# picospeaker.net
KiCad netlist of a schematic drawn in EAGLE
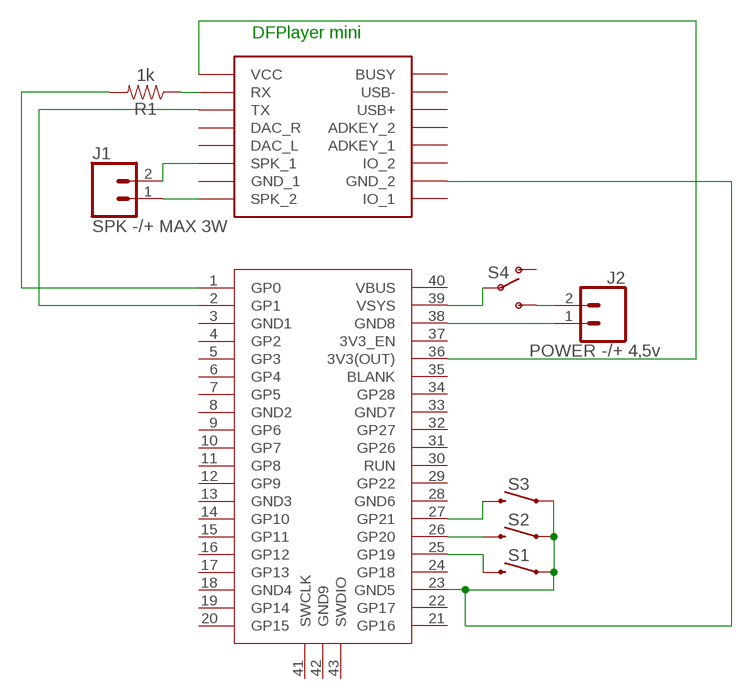
[diagram p0: schematic, sheet 1]

(export (version "E")
  (design (tool "Eeschema 10.0.6"))
  (components
    (comp (ref "J1")
      (value "SPK -/+ MAX 3W")
      (footprint "eagle-import:1X02")
      (libsource (lib "eagle-import") (part "CONN_02"))
    )
    (comp (ref "J2")
      (value "POWER -/+ 4,5v")
      (footprint "eagle-import:1X02")
      (libsource (lib "eagle-import") (part "CONN_02"))
    )
    (comp (ref "R1")
      (value "1k")
      (footprint "eagle-import:AXIAL-0.3-KIT")
      (libsource (lib "eagle-import") (part "1KOHM-HORIZ_KIT-1/4W-5%"))
    )
    (comp (ref "S1")
      (value "MOMENTARY-SWITCH-SPST-PTH-6.0MM-KIT")
      (footprint "eagle-import:TACTILE_SWITCH_PTH_6.0MM_KIT")
      (libsource (lib "eagle-import") (part "MOMENTARY-SWITCH-SPST-PTH-6.0MM-KIT"))
    )
    (comp (ref "S2")
      (value "MOMENTARY-SWITCH-SPST-PTH-6.0MM-KIT")
      (footprint "eagle-import:TACTILE_SWITCH_PTH_6.0MM_KIT")
      (libsource (lib "eagle-import") (part "MOMENTARY-SWITCH-SPST-PTH-6.0MM-KIT"))
    )
    (comp (ref "S3")
      (value "MOMENTARY-SWITCH-SPST-PTH-6.0MM-KIT")
      (footprint "eagle-import:TACTILE_SWITCH_PTH_6.0MM_KIT")
      (libsource (lib "eagle-import") (part "MOMENTARY-SWITCH-SPST-PTH-6.0MM-KIT"))
    )
    (comp (ref "S4")
      (value "SWITCH-SPDTSMD")
      (footprint "eagle-import:SWITCH_SPDT_SMD")
      (libsource (lib "eagle-import") (part "SWITCH-SPDTSMD"))
    )
    (comp (ref "U$1")
      (value "RASPBERRY-PI-PICO")
      (footprint "eagle-import:PICO-PKG-TH")
      (libsource (lib "eagle-import") (part "RASPBERRY-PI-PICO"))
    )
    (comp (ref "U$2")
      (value "DFPLAYER")
      (footprint "eagle-import:DFPLAYER")
      (libsource (lib "eagle-import") (part "DFPLAYER"))
    )
  )
  (nets
    (net (code "1") (name "/GND1") (class "Default")
      (node (ref "U$1") (pin "3") (pinfunction "GND1_3") (pintype "power_in"))
    )
    (net (code "2") (name "/GND2") (class "Default")
      (node (ref "U$1") (pin "8") (pinfunction "GND2_8") (pintype "power_in"))
    )
    (net (code "3") (name "/GND3") (class "Default")
      (node (ref "U$1") (pin "13") (pinfunction "GND3_13") (pintype "power_in"))
    )
    (net (code "4") (name "/GND4") (class "Default")
      (node (ref "U$1") (pin "18") (pinfunction "GND4_18") (pintype "power_in"))
    )
    (net (code "5") (name "/GND6") (class "Default")
      (node (ref "U$1") (pin "28") (pinfunction "GND6_28") (pintype "power_in"))
    )
    (net (code "6") (name "/GND7") (class "Default")
      (node (ref "U$1") (pin "33") (pinfunction "GND7_33") (pintype "power_in"))
    )
    (net (code "7") (name "/GND9") (class "Default")
      (node (ref "U$1") (pin "42") (pinfunction "GND9_42") (pintype "power_in"))
    )
    (net (code "8") (name "/VBUS") (class "Default")
      (node (ref "U$1") (pin "40") (pinfunction "VBUS_40") (pintype "power_in"))
    )
    (net (code "9") (name "Net-(R1-1)") (class "Default")
      (node (ref "R1") (pin "P$1") (pinfunction "1_P$1") (pintype "passive"))
      (node (ref "U$2") (pin "RX") (pinfunction "RX_RX") (pintype "bidirectional"))
    )
    (net (code "10") (name "Net-(R1-2)") (class "Default")
      (node (ref "R1") (pin "P$2") (pinfunction "2_P$2") (pintype "passive"))
      (node (ref "U$1") (pin "1") (pinfunction "GP0_1") (pintype "bidirectional"))
    )
    (net (code "11") (name "Net-(S1-2)") (class "Default")
      (node (ref "S1") (pin "3") (pinfunction "2_3") (pintype "passive"))
      (node (ref "U$1") (pin "25") (pinfunction "GP19_25") (pintype "bidirectional"))
    )
    (net (code "12") (name "Net-(S2-2)") (class "Default")
      (node (ref "S2") (pin "3") (pinfunction "2_3") (pintype "passive"))
      (node (ref "U$1") (pin "26") (pinfunction "GP20_26") (pintype "bidirectional"))
    )
    (net (code "13") (name "Net-(S3-2)") (class "Default")
      (node (ref "S3") (pin "3") (pinfunction "2_3") (pintype "passive"))
      (node (ref "U$1") (pin "27") (pinfunction "GP21_27") (pintype "bidirectional"))
    )
    (net (code "14") (name "Net-(S4-P)") (class "Default")
      (node (ref "S4") (pin "2") (pinfunction "P_2") (pintype "passive"))
      (node (ref "U$1") (pin "39") (pinfunction "VSYS_39") (pintype "power_in"))
    )
    (net (code "15") (name "Net-(S4-S)") (class "Default")
      (node (ref "J2") (pin "2") (pinfunction "2_2") (pintype "passive"))
      (node (ref "S4") (pin "3") (pinfunction "S_3") (pintype "passive"))
    )
    (net (code "16") (name "Net-(U$1-3V3(OUT))") (class "Default")
      (node (ref "U$1") (pin "36") (pinfunction "3V3(OUT)_36") (pintype "power_in"))
      (node (ref "U$2") (pin "VCC") (pinfunction "VCC_VCC") (pintype "bidirectional"))
    )
    (net (code "17") (name "Net-(U$1-GND5)") (class "Default")
      (node (ref "S1") (pin "1") (pinfunction "1_1") (pintype "passive"))
      (node (ref "S2") (pin "1") (pinfunction "1_1") (pintype "passive"))
      (node (ref "S3") (pin "1") (pinfunction "1_1") (pintype "passive"))
      (node (ref "U$1") (pin "23") (pinfunction "GND5_23") (pintype "power_in"))
      (node (ref "U$2") (pin "GND_2") (pinfunction "GND_2_GND_2") (pintype "bidirectional"))
    )
    (net (code "18") (name "Net-(U$1-GND8)") (class "Default")
      (node (ref "J2") (pin "1") (pinfunction "1_1") (pintype "passive"))
      (node (ref "U$1") (pin "38") (pinfunction "GND8_38") (pintype "power_in"))
    )
    (net (code "19") (name "Net-(U$1-GP1)") (class "Default")
      (node (ref "U$1") (pin "2") (pinfunction "GP1_2") (pintype "bidirectional"))
      (node (ref "U$2") (pin "TX") (pinfunction "TX_TX") (pintype "bidirectional"))
    )
    (net (code "20") (name "Net-(U$2-SPK_1)") (class "Default")
      (node (ref "J1") (pin "2") (pinfunction "2_2") (pintype "passive"))
      (node (ref "U$2") (pin "SPK1") (pinfunction "SPK_1_SPK1") (pintype "bidirectional"))
    )
    (net (code "21") (name "Net-(U$2-SPK_2)") (class "Default")
      (node (ref "J1") (pin "1") (pinfunction "1_1") (pintype "passive"))
      (node (ref "U$2") (pin "SPK2") (pinfunction "SPK_2_SPK2") (pintype "bidirectional"))
    )
    (net (code "22") (name "unconnected-(S4-O-Pad1)") (class "Default")
      (node (ref "S4") (pin "1") (pinfunction "O_1") (pintype "passive"))
    )
    (net (code "23") (name "unconnected-(U$1-3V3_EN-Pad37)") (class "Default")
      (node (ref "U$1") (pin "37") (pinfunction "3V3_EN_37") (pintype "bidirectional"))
    )
    (net (code "24") (name "unconnected-(U$1-BLANK-Pad35)") (class "Default")
      (node (ref "U$1") (pin "35") (pinfunction "BLANK_35") (pintype "bidirectional"))
    )
    (net (code "25") (name "unconnected-(U$1-GP2-Pad4)") (class "Default")
      (node (ref "U$1") (pin "4") (pinfunction "GP2_4") (pintype "bidirectional"))
    )
    (net (code "26") (name "unconnected-(U$1-GP3-Pad5)") (class "Default")
      (node (ref "U$1") (pin "5") (pinfunction "GP3_5") (pintype "bidirectional"))
    )
    (net (code "27") (name "unconnected-(U$1-GP4-Pad6)") (class "Default")
      (node (ref "U$1") (pin "6") (pinfunction "GP4_6") (pintype "bidirectional"))
    )
    (net (code "28") (name "unconnected-(U$1-GP5-Pad7)") (class "Default")
      (node (ref "U$1") (pin "7") (pinfunction "GP5_7") (pintype "bidirectional"))
    )
    (net (code "29") (name "unconnected-(U$1-GP6-Pad9)") (class "Default")
      (node (ref "U$1") (pin "9") (pinfunction "GP6_9") (pintype "bidirectional"))
    )
    (net (code "30") (name "unconnected-(U$1-GP7-Pad10)") (class "Default")
      (node (ref "U$1") (pin "10") (pinfunction "GP7_10") (pintype "bidirectional"))
    )
    (net (code "31") (name "unconnected-(U$1-GP8-Pad11)") (class "Default")
      (node (ref "U$1") (pin "11") (pinfunction "GP8_11") (pintype "bidirectional"))
    )
    (net (code "32") (name "unconnected-(U$1-GP9-Pad12)") (class "Default")
      (node (ref "U$1") (pin "12") (pinfunction "GP9_12") (pintype "bidirectional"))
    )
    (net (code "33") (name "unconnected-(U$1-GP10-Pad14)") (class "Default")
      (node (ref "U$1") (pin "14") (pinfunction "GP10_14") (pintype "bidirectional"))
    )
    (net (code "34") (name "unconnected-(U$1-GP11-Pad15)") (class "Default")
      (node (ref "U$1") (pin "15") (pinfunction "GP11_15") (pintype "bidirectional"))
    )
    (net (code "35") (name "unconnected-(U$1-GP12-Pad16)") (class "Default")
      (node (ref "U$1") (pin "16") (pinfunction "GP12_16") (pintype "bidirectional"))
    )
    (net (code "36") (name "unconnected-(U$1-GP13-Pad17)") (class "Default")
      (node (ref "U$1") (pin "17") (pinfunction "GP13_17") (pintype "bidirectional"))
    )
    (net (code "37") (name "unconnected-(U$1-GP14-Pad19)") (class "Default")
      (node (ref "U$1") (pin "19") (pinfunction "GP14_19") (pintype "bidirectional"))
    )
    (net (code "38") (name "unconnected-(U$1-GP15-Pad20)") (class "Default")
      (node (ref "U$1") (pin "20") (pinfunction "GP15_20") (pintype "bidirectional"))
    )
    (net (code "39") (name "unconnected-(U$1-GP16-Pad21)") (class "Default")
      (node (ref "U$1") (pin "21") (pinfunction "GP16_21") (pintype "bidirectional"))
    )
    (net (code "40") (name "unconnected-(U$1-GP17-Pad22)") (class "Default")
      (node (ref "U$1") (pin "22") (pinfunction "GP17_22") (pintype "bidirectional"))
    )
    (net (code "41") (name "unconnected-(U$1-GP18-Pad24)") (class "Default")
      (node (ref "U$1") (pin "24") (pinfunction "GP18_24") (pintype "bidirectional"))
    )
    (net (code "42") (name "unconnected-(U$1-GP22-Pad29)") (class "Default")
      (node (ref "U$1") (pin "29") (pinfunction "GP22_29") (pintype "bidirectional"))
    )
    (net (code "43") (name "unconnected-(U$1-GP26-Pad31)") (class "Default")
      (node (ref "U$1") (pin "31") (pinfunction "GP26_31") (pintype "bidirectional"))
    )
    (net (code "44") (name "unconnected-(U$1-GP27-Pad32)") (class "Default")
      (node (ref "U$1") (pin "32") (pinfunction "GP27_32") (pintype "bidirectional"))
    )
    (net (code "45") (name "unconnected-(U$1-GP28-Pad34)") (class "Default")
      (node (ref "U$1") (pin "34") (pinfunction "GP28_34") (pintype "bidirectional"))
    )
    (net (code "46") (name "unconnected-(U$1-RUN-Pad30)") (class "Default")
      (node (ref "U$1") (pin "30") (pinfunction "RUN_30") (pintype "bidirectional"))
    )
    (net (code "47") (name "unconnected-(U$1-SWCLK-Pad41)") (class "Default")
      (node (ref "U$1") (pin "41") (pinfunction "SWCLK_41") (pintype "bidirectional"))
    )
    (net (code "48") (name "unconnected-(U$1-SWDIO-Pad43)") (class "Default")
      (node (ref "U$1") (pin "43") (pinfunction "SWDIO_43") (pintype "bidirectional"))
    )
    (net (code "49") (name "unconnected-(U$2-ADKEY_1-PadADKEY1)") (class "Default")
      (node (ref "U$2") (pin "ADKEY1") (pinfunction "ADKEY_1_ADKEY1") (pintype "bidirectional"))
    )
    (net (code "50") (name "unconnected-(U$2-ADKEY_2-PadADKEY2)") (class "Default")
      (node (ref "U$2") (pin "ADKEY2") (pinfunction "ADKEY_2_ADKEY2") (pintype "bidirectional"))
    )
    (net (code "51") (name "unconnected-(U$2-IO_1-PadIO1)") (class "Default")
      (node (ref "U$2") (pin "IO1") (pinfunction "IO_1_IO1") (pintype "bidirectional"))
    )
    (net (code "52") (name "unconnected-(U$2-IO_2-PadIO2)") (class "Default")
      (node (ref "U$2") (pin "IO2") (pinfunction "IO_2_IO2") (pintype "bidirectional"))
    )
    (net (code "53") (name "unconnected-(U$2-PadBUSY)") (class "Default")
      (node (ref "U$2") (pin "BUSY") (pinfunction "BUSY_BUSY") (pintype "bidirectional"))
    )
    (net (code "54") (name "unconnected-(U$2-PadDAC_L)") (class "Default")
      (node (ref "U$2") (pin "DAC_L") (pinfunction "DAC_L_DAC_L") (pintype "bidirectional"))
    )
    (net (code "55") (name "unconnected-(U$2-PadDAC_R)") (class "Default")
      (node (ref "U$2") (pin "DAC_R") (pinfunction "DAC_R_DAC_R") (pintype "bidirectional"))
    )
    (net (code "56") (name "unconnected-(U$2-PadGND_1)") (class "Default")
      (node (ref "U$2") (pin "GND_1") (pinfunction "GND_1_GND_1") (pintype "bidirectional"))
    )
    (net (code "57") (name "unconnected-(U$2-PadUSB+)") (class "Default")
      (node (ref "U$2") (pin "USB+") (pinfunction "USB+_USB+") (pintype "bidirectional"))
    )
    (net (code "58") (name "unconnected-(U$2-PadUSB-)") (class "Default")
      (node (ref "U$2") (pin "USB-") (pinfunction "USB-_USB-") (pintype "bidirectional"))
    )
  )
)
